# CindyLou_Main_Board_copy_2023-08-16.net
KiCad netlist of a schematic drawn in Altium Designer
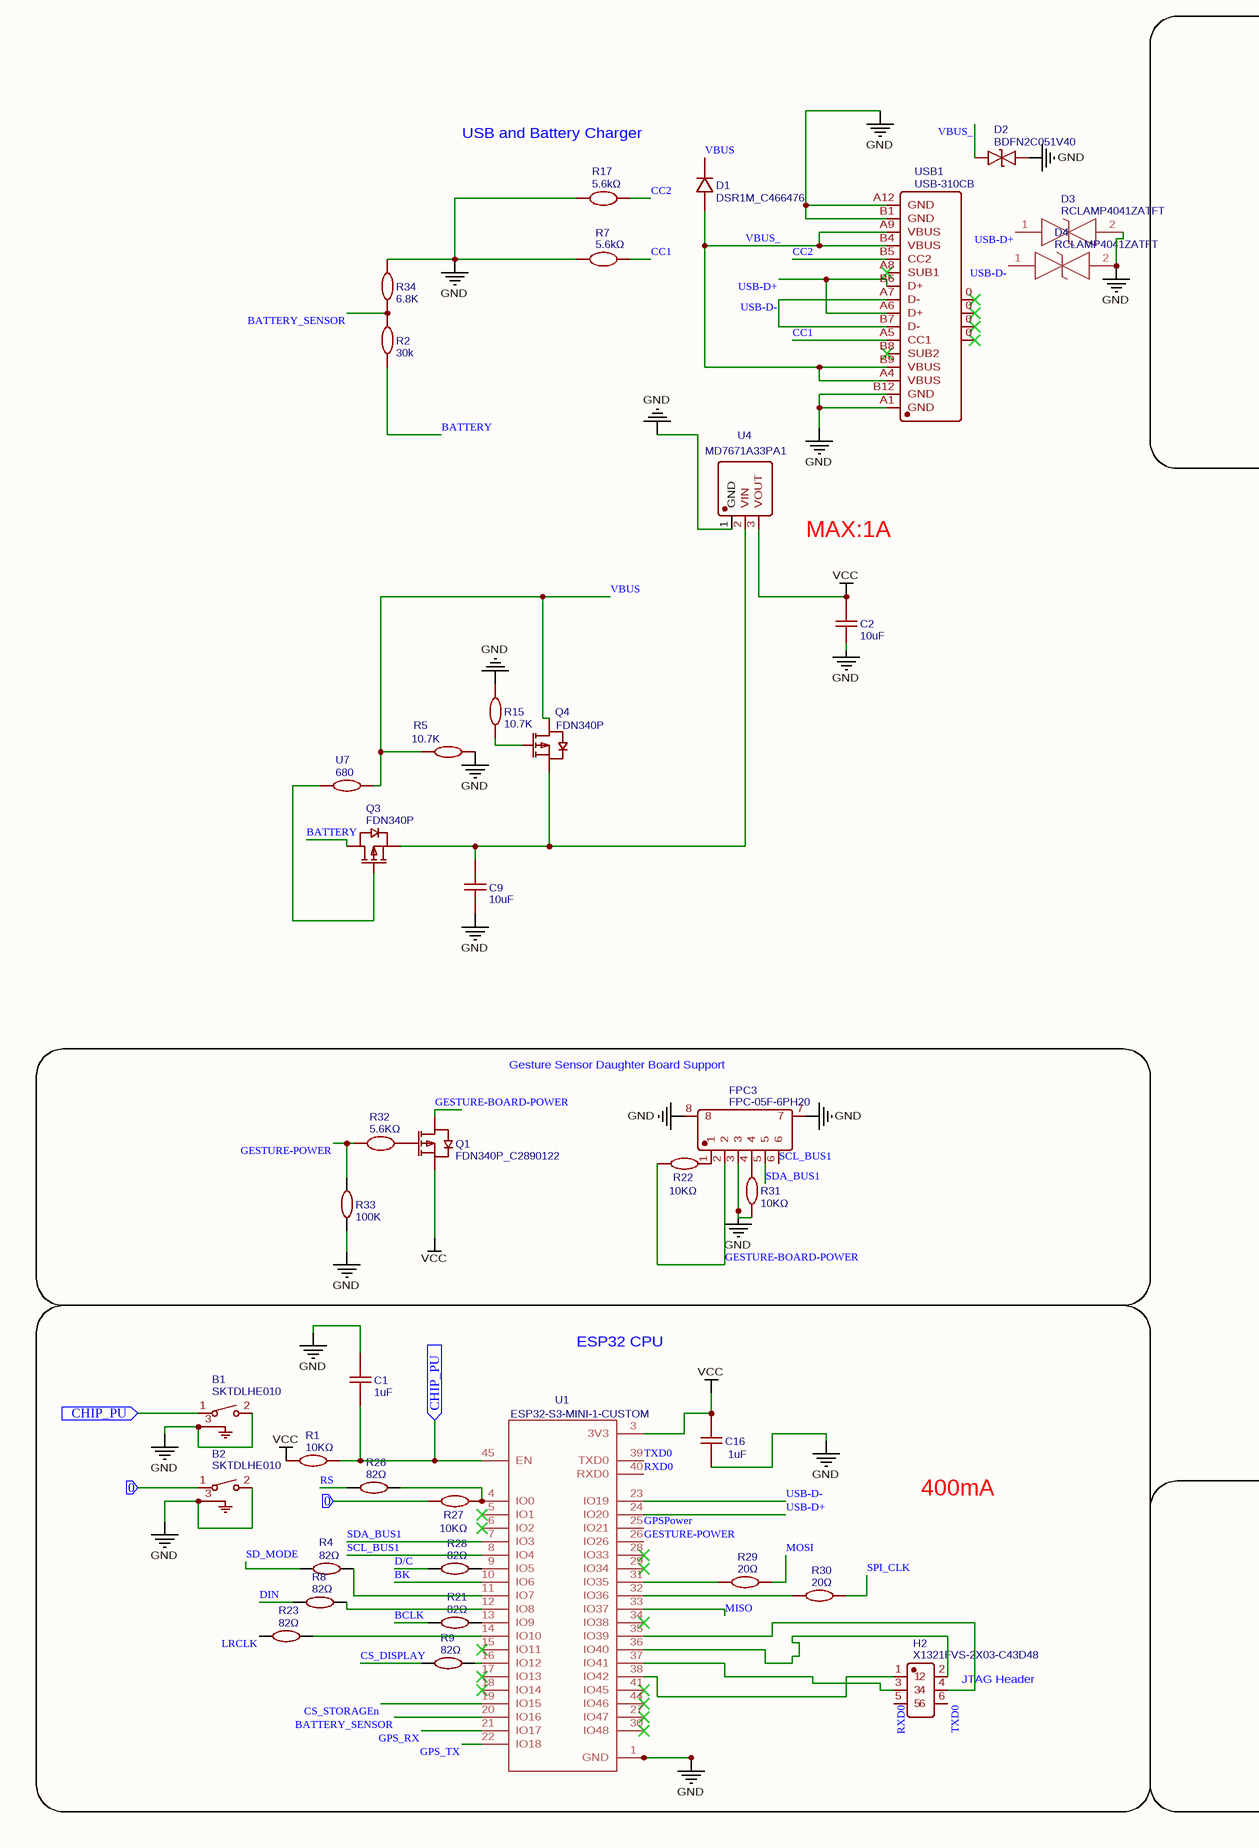
[diagram p0: CindyLou Main Board copy_2023-08-16.schdoc, left]
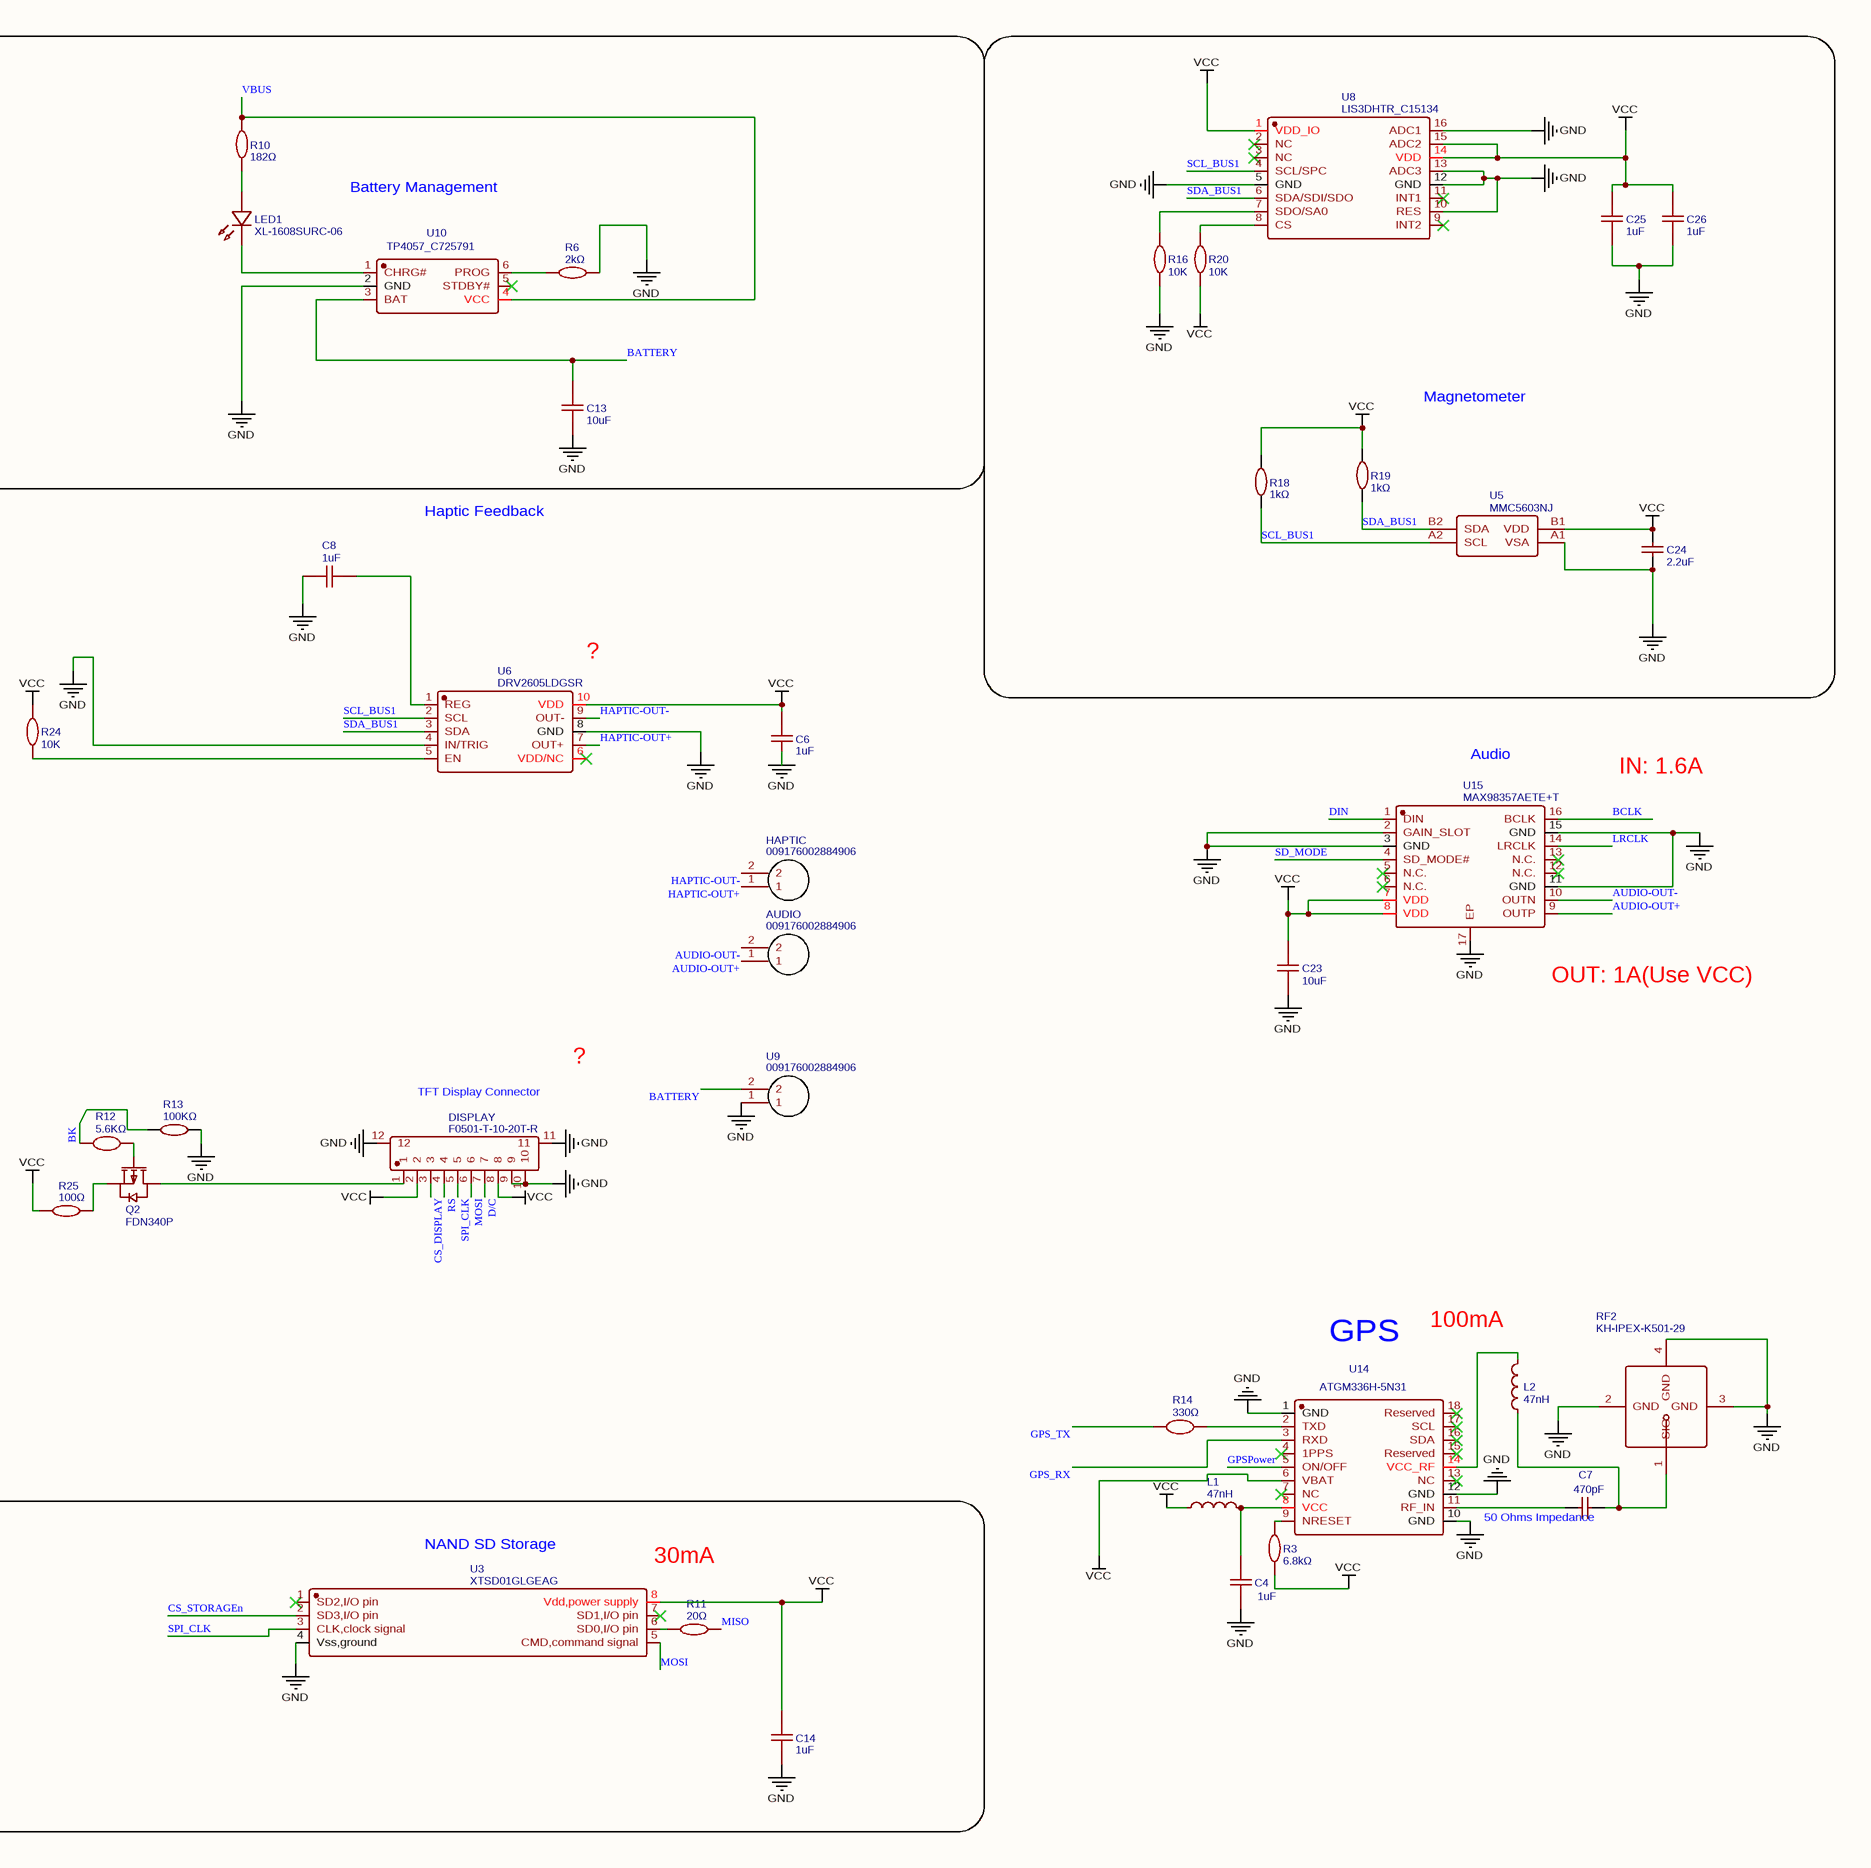
[diagram p1: CindyLou Main Board copy_2023-08-16.schdoc, right]

(export (version "E")
  (design (tool "Eeschema 10.0.6"))
  (components
    (comp (ref "AUDIO")
      (value "009176002884906")
      (footprint "009176002884906")
      (fields (field (name "CONTRIBUTOR") "Av448"))
      (libsource (lib "altium-import") (part "root_0_009176002884906_"))
    )
    (comp (ref "B1")
      (value "SKTDLHE010")
      (footprint "KEY-SMD_SKTDLHE010")
      (fields (field (name "MANUFACTURER") "ALPS Electric") (field (name "CONTRIBUTOR") "LCSC"))
      (libsource (lib "altium-import") (part "root_0_SKTDLHE010_"))
    )
    (comp (ref "B2")
      (value "SKTDLHE010")
      (footprint "KEY-SMD_SKTDLHE010")
      (fields (field (name "MANUFACTURER") "ALPS Electric") (field (name "CONTRIBUTOR") "LCSC"))
      (libsource (lib "altium-import") (part "root_0_SKTDLHE010_"))
    )
    (comp (ref "C1")
      (value "1uF")
      (footprint "C0402")
      (fields
        (field (name "MANUFACTURER") "muRata(村田)")
        (field (name "MANUFACTURER PART") "GRT155R70J105KE01D")
        (field (name "CONTRIBUTOR") "LCSC")
      )
      (libsource (lib "altium-import") (part "root_1_1uF_"))
    )
    (comp (ref "C2")
      (value "10uF")
      (footprint "C0402")
      (fields
        (field (name "MANUFACTURER") "SAMSUNG(三星)")
        (field (name "MANUFACTURER PART") "CL05A106MQ5NUNZ")
        (field (name "CONTRIBUTOR") "LCSC")
      )
      (libsource (lib "altium-import") (part "root_3_10uF_"))
    )
    (comp (ref "C4")
      (value "1uF")
      (footprint "C0402")
      (fields
        (field (name "MANUFACTURER") "muRata(村田)")
        (field (name "MANUFACTURER PART") "GRT155R70J105KE01D")
        (field (name "CONTRIBUTOR") "LCSC")
      )
      (libsource (lib "altium-import") (part "root_1_1uF_"))
    )
    (comp (ref "C6")
      (value "1uF")
      (footprint "C0402")
      (fields
        (field (name "MANUFACTURER") "muRata(村田)")
        (field (name "MANUFACTURER PART") "GRT155R70J105KE01D")
        (field (name "CONTRIBUTOR") "LCSC")
      )
      (libsource (lib "altium-import") (part "root_1_1uF_"))
    )
    (comp (ref "C7")
      (value "470pF")
      (footprint "C0201")
      (fields (field (name "MANUFACTURER PART") "0201B471K500NT") (field (name "MANUFACTURER") "FH"))
      (libsource (lib "altium-import") (part "root_0_470pF_"))
    )
    (comp (ref "C8")
      (value "1uF")
      (footprint "C0201")
      (fields
        (field (name "MANUFACTURER") "SANYEAR")
        (field (name "MANUFACTURER PART") "C0201X5R105M6R3NT")
        (field (name "CONTRIBUTOR") "LCSC")
      )
      (libsource (lib "altium-import") (part "root_0_1uF_"))
    )
    (comp (ref "C9")
      (value "10uF")
      (footprint "C0402")
      (fields
        (field (name "MANUFACTURER") "SAMSUNG(三星)")
        (field (name "MANUFACTURER PART") "CL05A106MQ5NUNZ")
        (field (name "CONTRIBUTOR") "LCSC")
      )
      (libsource (lib "altium-import") (part "root_1_10uF_"))
    )
    (comp (ref "C13")
      (value "10uF")
      (footprint "C0402")
      (fields
        (field (name "MANUFACTURER") "SAMSUNG(三星)")
        (field (name "MANUFACTURER PART") "CL05A106MQ5NUNZ")
        (field (name "CONTRIBUTOR") "LCSC")
      )
      (libsource (lib "altium-import") (part "root_1_10uF_"))
    )
    (comp (ref "C14")
      (value "1uF")
      (footprint "C0402")
      (fields
        (field (name "MANUFACTURER") "muRata(村田)")
        (field (name "MANUFACTURER PART") "GRT155R70J105KE01D")
        (field (name "CONTRIBUTOR") "LCSC")
      )
      (libsource (lib "altium-import") (part "root_1_1uF_"))
    )
    (comp (ref "C16")
      (value "1uF")
      (footprint "C0402")
      (fields
        (field (name "MANUFACTURER") "muRata(村田)")
        (field (name "MANUFACTURER PART") "GRT155R70J105KE01D")
        (field (name "CONTRIBUTOR") "LCSC")
      )
      (libsource (lib "altium-import") (part "root_1_1uF_"))
    )
    (comp (ref "C23")
      (value "10uF")
      (footprint "C0402")
      (fields
        (field (name "MANUFACTURER") "SAMSUNG(三星)")
        (field (name "MANUFACTURER PART") "CL05A106MQ5NUNZ")
        (field (name "CONTRIBUTOR") "LCSC")
      )
      (libsource (lib "altium-import") (part "root_1_10uF_"))
    )
    (comp (ref "C24")
      (value "2.2uF")
      (footprint "C0402")
      (fields (field (name "MANUFACTURER PART") "GRM155R61A225KE95D") (field (name "MANUFACTURER") "MuRata"))
      (libsource (lib "altium-import") (part "root_1_2.2uF_"))
    )
    (comp (ref "C25")
      (value "1uF")
      (footprint "C0402")
      (fields
        (field (name "MANUFACTURER") "muRata(村田)")
        (field (name "MANUFACTURER PART") "GRT155R70J105KE01D")
        (field (name "CONTRIBUTOR") "LCSC")
      )
      (libsource (lib "altium-import") (part "root_1_1uF_"))
    )
    (comp (ref "C26")
      (value "1uF")
      (footprint "C0402")
      (fields
        (field (name "MANUFACTURER") "muRata(村田)")
        (field (name "MANUFACTURER PART") "GRT155R70J105KE01D")
        (field (name "CONTRIBUTOR") "LCSC")
      )
      (libsource (lib "altium-import") (part "root_1_1uF_"))
    )
    (comp (ref "D1")
      (value "DSR1M_C466476")
      (footprint "SOD-123FL_L2.8-W1.8-LS3.7-RD")
      (fields
        (field (name "MANUFACTURER") "High Diode(海德)")
        (field (name "MANUFACTURER PART") "DSR1M")
        (field (name "CONTRIBUTOR") "LCSC")
      )
      (libsource (lib "altium-import") (part "root_3_DSR1M_C466476_"))
    )
    (comp (ref "D2")
      (value "BDFN2C051V40")
      (footprint "DFN-SMD_L1.0-W0.6-BI")
      (fields (field (name "MANUFACTURER") "BORN(伯恩半导体)") (field (name "CONTRIBUTOR") "LCSC"))
      (libsource (lib "altium-import") (part "root_0_BDFN2C051V40_"))
    )
    (comp (ref "D3")
      (value "RCLAMP4041ZATFT")
      (footprint "RCLAMP4021ZATFT")
      (fields (field (name "CONTRIBUTOR") "dparker"))
      (libsource (lib "altium-import") (part "root_0_RCLAMP4041ZATFT_"))
    )
    (comp (ref "D4")
      (value "RCLAMP4041ZATFT")
      (footprint "RCLAMP4021ZATFT")
      (fields (field (name "CONTRIBUTOR") "dparker"))
      (libsource (lib "altium-import") (part "root_0_RCLAMP4041ZATFT_"))
    )
    (comp (ref "DISPLAY")
      (value "F0501-T-10-20T-R")
      (footprint "FPC-SMD_F0501-T-10-20T-R")
      (fields (field (name "MANUFACTURER") "XFCN(兴飞)") (field (name "CONTRIBUTOR") "LCSC"))
      (libsource (lib "altium-import") (part "root_1_F0501-T-10-20T-R_"))
    )
    (comp (ref "FPC3")
      (value "FPC-05F-6PH20")
      (footprint "FPC-SMD_6P-P0.50_XUNPU_FPC-05F-6PH20")
      (fields (field (name "MANUFACTURER") "XUNPU(讯普)") (field (name "CONTRIBUTOR") "LCSC"))
      (libsource (lib "altium-import") (part "root_1_FPC-05F-6PH20_"))
    )
    (comp (ref "H2")
      (value "X1321FVS-2X03-C43D48")
      (footprint "HDR-SMD_6P-P1.27-V-F-R2-C3-LS4.8")
      (fields
        (field (name "MANUFACTURER") "XKB Connectivity(中国星坤)")
        (field (name "MANUFACTURER PART") "X1321FVS-2x03-C43D48")
        (field (name "CONTRIBUTOR") "LCSC")
      )
      (libsource (lib "altium-import") (part "root_0_X1321FVS-2X03-C43D48_"))
    )
    (comp (ref "HAPTIC")
      (value "009176002884906")
      (footprint "009176002884906")
      (fields (field (name "CONTRIBUTOR") "Av448"))
      (libsource (lib "altium-import") (part "root_0_009176002884906_"))
    )
    (comp (ref "L1")
      (value "47nH")
      (footprint "L0201")
      (fields
        (field (name "MANUFACTURER") "TDK")
        (field (name "MANUFACTURER PART") "MLG0603P47NHT000")
        (field (name "CONTRIBUTOR") "LCSC")
      )
      (libsource (lib "altium-import") (part "root_0_47nH_"))
    )
    (comp (ref "L2")
      (value "47nH")
      (footprint "L0201")
      (fields
        (field (name "MANUFACTURER") "TDK")
        (field (name "MANUFACTURER PART") "MLG0603P47NHT000")
        (field (name "CONTRIBUTOR") "LCSC")
      )
      (libsource (lib "altium-import") (part "root_1_47nH_"))
    )
    (comp (ref "LED1")
      (value "XL-1608SURC-06")
      (footprint "LED0603-RD_RED")
      (fields (field (name "MANUFACTURER") "XINGLIGHT(成兴光)") (field (name "CONTRIBUTOR") "LCSC"))
      (libsource (lib "altium-import") (part "root_1_XL-1608SURC-06_"))
    )
    (comp (ref "Q1")
      (value "FDN340P_C2890122")
      (footprint "SOT-23-3_L2.9-W1.3-P1.90-LS2.4-BR")
      (fields
        (field (name "MANUFACTURER") "TECH PUBLIC(台舟)")
        (field (name "MANUFACTURER PART") "FDN340P")
        (field (name "CONTRIBUTOR") "LCSC")
      )
      (libsource (lib "altium-import") (part "root_0_FDN340P_C2890122_"))
    )
    (comp (ref "Q2")
      (value "FDN340P")
      (footprint "SOT-23-3_L2.9-W1.3-P1.90-LS2.4-BR")
      (fields (field (name "MANUFACTURER") "TECH PUBLIC(台舟)") (field (name "CONTRIBUTOR") "LCSC"))
      (libsource (lib "altium-import") (part "root_3_FDN340P_"))
    )
    (comp (ref "Q3")
      (value "FDN340P")
      (footprint "SOT-23-3_L2.9-W1.3-P1.90-LS2.4-BR")
      (fields (field (name "MANUFACTURER") "TECH PUBLIC(台舟)") (field (name "CONTRIBUTOR") "LCSC"))
      (libsource (lib "altium-import") (part "root_1_FDN340P_"))
    )
    (comp (ref "Q4")
      (value "FDN340P")
      (footprint "SOT-23-3_L2.9-W1.3-P1.90-LS2.4-BR")
      (fields (field (name "MANUFACTURER") "TECH PUBLIC(台舟)") (field (name "CONTRIBUTOR") "LCSC"))
      (libsource (lib "altium-import") (part "root_0_FDN340P_"))
    )
    (comp (ref "R1")
      (value "10KΩ")
      (footprint "R0402")
      (fields
        (field (name "MANUFACTURER") "Stackpole Elec")
        (field (name "MANUFACTURER PART") "RNCF0402BTE10K0")
        (field (name "CONTRIBUTOR") "LCSC")
      )
      (libsource (lib "altium-import") (part "root_0_10KΩ_"))
    )
    (comp (ref "R2")
      (value "30k")
      (footprint "R0402")
      (fields
        (field (name "MANUFACTURER") "Susumu")
        (field (name "MANUFACTURER PART") "RR0510P-303-D")
        (field (name "CONTRIBUTOR") "LCSC")
      )
      (libsource (lib "altium-import") (part "root_1_30k_"))
    )
    (comp (ref "R3")
      (value "6.8kΩ")
      (footprint "R0402")
      (fields
        (field (name "MANUFACTURER") "ResistorToday")
        (field (name "MANUFACTURER PART") "AECR0402F6K80K9")
        (field (name "CONTRIBUTOR") "LCSC")
      )
      (libsource (lib "altium-import") (part "root_1_6.8kΩ_"))
    )
    (comp (ref "R4")
      (value "82Ω")
      (footprint "R0201")
      (fields (field (name "MANUFACTURER") "YAGEO") (field (name "MANUFACTURER PART") "AF0201JR-0782RL"))
      (libsource (lib "altium-import") (part "root_0_82Ω_"))
    )
    (comp (ref "R5")
      (value "10.7K")
      (footprint "R0402")
      (fields (field (name "MANUFACTURER PART") "SCR0402F10K7") (field (name "CONTRIBUTOR") "LCSC"))
      (libsource (lib "altium-import") (part "root_0_10.7K_"))
    )
    (comp (ref "R6")
      (value "2kΩ")
      (footprint "R0201")
      (fields
        (field (name "MANUFACTURER") "Uniroyal Elec")
        (field (name "MANUFACTURER PART") "0201WMF2001TEE")
        (field (name "CONTRIBUTOR") "LCSC")
      )
      (libsource (lib "altium-import") (part "root_0_2kΩ_"))
    )
    (comp (ref "R7")
      (value "5.6kΩ")
      (footprint "R0201")
      (fields
        (field (name "MANUFACTURER") "UNI-ROYAL(Uniroyal Elec)")
        (field (name "MANUFACTURER PART") "NQ01WMJ0562TEE")
        (field (name "CONTRIBUTOR") "LCSC")
      )
      (libsource (lib "altium-import") (part "root_0_5.6kΩ_"))
    )
    (comp (ref "R8")
      (value "82Ω")
      (footprint "R0201")
      (fields (field (name "MANUFACTURER") "YAGEO") (field (name "MANUFACTURER PART") "AF0201JR-0782RL"))
      (libsource (lib "altium-import") (part "root_0_82Ω_"))
    )
    (comp (ref "R9")
      (value "82Ω")
      (footprint "R0201")
      (fields (field (name "MANUFACTURER") "YAGEO") (field (name "MANUFACTURER PART") "AF0201JR-0782RL"))
      (libsource (lib "altium-import") (part "root_0_82Ω_"))
    )
    (comp (ref "R10")
      (value "182Ω")
      (footprint "R0402")
      (fields
        (field (name "MANUFACTURER") "Multicomp")
        (field (name "MANUFACTURER PART") "MCWR04X1820FTL")
        (field (name "CONTRIBUTOR") "LCSC")
      )
      (libsource (lib "altium-import") (part "root_1_182Ω_"))
    )
    (comp (ref "R11")
      (value "20Ω")
      (footprint "R0201")
      (fields (field (name "MANUFACTURER PART") "AC0201FR-0720RL") (field (name "CONTRIBUTOR") "LCSC"))
      (libsource (lib "altium-import") (part "root_0_20Ω_"))
    )
    (comp (ref "R12")
      (value "5.6KΩ")
      (footprint "R0402")
      (fields (field (name "MANUFACTURER PART") "RMC04025.6K5%N") (field (name "CONTRIBUTOR") "LCSC"))
      (libsource (lib "altium-import") (part "root_0_5.6KΩ_"))
    )
    (comp (ref "R13")
      (value "100KΩ")
      (footprint "R0402")
      (fields (field (name "MANUFACTURER") "YAGEO") (field (name "MANUFACTURER PART") "RC0402FR-07100KL"))
      (libsource (lib "altium-import") (part "root_2_100KΩ_"))
    )
    (comp (ref "R14")
      (value "330Ω")
      (footprint "R0201")
      (fields
        (field (name "MANUFACTURER") "UNI-ROYAL(Uniroyal Elec)")
        (field (name "MANUFACTURER PART") "0201WMJ0331TEE")
        (field (name "CONTRIBUTOR") "LCSC")
      )
      (libsource (lib "altium-import") (part "root_0_330Ω_"))
    )
    (comp (ref "R15")
      (value "10.7K")
      (footprint "R0402")
      (fields (field (name "MANUFACTURER PART") "SCR0402F10K7") (field (name "CONTRIBUTOR") "LCSC"))
      (libsource (lib "altium-import") (part "root_1_10.7K_"))
    )
    (comp (ref "R16")
      (value "10K")
      (footprint "R0402")
      (fields
        (field (name "MANUFACTURER") "ResistorToday")
        (field (name "MANUFACTURER PART") "AECR0402F10K0K9")
        (field (name "CONTRIBUTOR") "LCSC")
      )
      (libsource (lib "altium-import") (part "root_1_10K_"))
    )
    (comp (ref "R17")
      (value "5.6kΩ")
      (footprint "R0201")
      (fields
        (field (name "MANUFACTURER") "UNI-ROYAL(Uniroyal Elec)")
        (field (name "MANUFACTURER PART") "NQ01WMJ0562TEE")
        (field (name "CONTRIBUTOR") "LCSC")
      )
      (libsource (lib "altium-import") (part "root_2_5.6kΩ_"))
    )
    (comp (ref "R18")
      (value "1kΩ")
      (footprint "R0402")
      (fields
        (field (name "MANUFACTURER") "UNI-ROYAL(厚声)")
        (field (name "MANUFACTURER PART") "0402WGJ0102TCE")
      )
      (libsource (lib "altium-import") (part "root_1_1kΩ_"))
    )
    (comp (ref "R19")
      (value "1kΩ")
      (footprint "R0402")
      (fields
        (field (name "MANUFACTURER") "UNI-ROYAL(厚声)")
        (field (name "MANUFACTURER PART") "0402WGJ0102TCE")
      )
      (libsource (lib "altium-import") (part "root_1_1kΩ_"))
    )
    (comp (ref "R20")
      (value "10K")
      (footprint "R0402")
      (fields
        (field (name "MANUFACTURER") "ResistorToday")
        (field (name "MANUFACTURER PART") "AECR0402F10K0K9")
        (field (name "CONTRIBUTOR") "LCSC")
      )
      (libsource (lib "altium-import") (part "root_1_10K_"))
    )
    (comp (ref "R21")
      (value "82Ω")
      (footprint "R0201")
      (fields (field (name "MANUFACTURER") "YAGEO") (field (name "MANUFACTURER PART") "AF0201JR-0782RL"))
      (libsource (lib "altium-import") (part "root_0_82Ω_"))
    )
    (comp (ref "R22")
      (value "10KΩ")
      (footprint "R0402")
      (fields
        (field (name "MANUFACTURER") "Stackpole Elec")
        (field (name "MANUFACTURER PART") "RNCF0402BTE10K0")
        (field (name "CONTRIBUTOR") "LCSC")
      )
      (libsource (lib "altium-import") (part "root_0_10KΩ_"))
    )
    (comp (ref "R23")
      (value "82Ω")
      (footprint "R0201")
      (fields (field (name "MANUFACTURER") "YAGEO") (field (name "MANUFACTURER PART") "AF0201JR-0782RL"))
      (libsource (lib "altium-import") (part "root_0_82Ω_"))
    )
    (comp (ref "R24")
      (value "10K")
      (footprint "R0402")
      (fields
        (field (name "MANUFACTURER") "ResistorToday")
        (field (name "MANUFACTURER PART") "AECR0402F10K0K9")
        (field (name "CONTRIBUTOR") "LCSC")
      )
      (libsource (lib "altium-import") (part "root_1_10K_"))
    )
    (comp (ref "R25")
      (value "100Ω")
      (footprint "R0402")
      (fields
        (field (name "MANUFACTURER") "ResistorToday")
        (field (name "MANUFACTURER PART") "PTFR0402B100RN9")
        (field (name "CONTRIBUTOR") "LCSC")
      )
      (libsource (lib "altium-import") (part "root_0_100Ω_"))
    )
    (comp (ref "R26")
      (value "82Ω")
      (footprint "R0201")
      (fields (field (name "MANUFACTURER") "YAGEO") (field (name "MANUFACTURER PART") "AF0201JR-0782RL"))
      (libsource (lib "altium-import") (part "root_0_82Ω_"))
    )
    (comp (ref "R27")
      (value "10KΩ")
      (footprint "R0402")
      (fields
        (field (name "MANUFACTURER") "Stackpole Elec")
        (field (name "MANUFACTURER PART") "RNCF0402BTE10K0")
        (field (name "CONTRIBUTOR") "LCSC")
      )
      (libsource (lib "altium-import") (part "root_0_10KΩ_"))
    )
    (comp (ref "R28")
      (value "82Ω")
      (footprint "R0201")
      (fields (field (name "MANUFACTURER") "YAGEO") (field (name "MANUFACTURER PART") "AF0201JR-0782RL"))
      (libsource (lib "altium-import") (part "root_0_82Ω_"))
    )
    (comp (ref "R29")
      (value "20Ω")
      (footprint "R0201")
      (fields (field (name "CONTRIBUTOR") "LCSC"))
      (libsource (lib "altium-import") (part "root_0_20Ω_"))
    )
    (comp (ref "R30")
      (value "20Ω")
      (footprint "R0201")
      (fields (field (name "CONTRIBUTOR") "LCSC"))
      (libsource (lib "altium-import") (part "root_0_20Ω_"))
    )
    (comp (ref "R31")
      (value "10KΩ")
      (footprint "R0402")
      (fields
        (field (name "MANUFACTURER") "Stackpole Elec")
        (field (name "MANUFACTURER PART") "RNCF0402BTE10K0")
        (field (name "CONTRIBUTOR") "LCSC")
      )
      (libsource (lib "altium-import") (part "root_1_10KΩ_"))
    )
    (comp (ref "R32")
      (value "5.6KΩ")
      (footprint "R0402")
      (fields (field (name "MANUFACTURER PART") "RMC04025.6K5%N") (field (name "CONTRIBUTOR") "LCSC"))
      (libsource (lib "altium-import") (part "root_0_5.6KΩ_"))
    )
    (comp (ref "R33")
      (value "100K")
      (footprint "R0402")
      (fields (field (name "MANUFACTURER") "YAGEO") (field (name "MANUFACTURER PART") "RC0402FR-07100KL"))
      (libsource (lib "altium-import") (part "root_1_100K_"))
    )
    (comp (ref "R34")
      (value "6.8K")
      (footprint "R0402")
      (fields
        (field (name "MANUFACTURER") "ResistorToday")
        (field (name "MANUFACTURER PART") "HPCR0402F6K80K9")
        (field (name "CONTRIBUTOR") "LCSC")
      )
      (libsource (lib "altium-import") (part "root_1_6.8K_"))
    )
    (comp (ref "RF2")
      (value "KH-IPEX-K501-29")
      (footprint "ANT-SMD_KH-IPEX-K501-29")
      (fields (field (name "MANUFACTURER") "Shenzhen Kinghelm Elec") (field (name "CONTRIBUTOR") "LCSC"))
      (libsource (lib "altium-import") (part "root_0_KH-IPEX-K501-29_"))
    )
    (comp (ref "U1")
      (value "ESP32-S3-MINI-1-CUSTOM")
      (footprint "XCVR_ESP32-S3-MINI-1-N8-CUSTOM")
      (fields (field (name "CONTRIBUTOR") "Stefan Ravn van Overeem"))
      (libsource (lib "altium-import") (part "root_0_ESP32-S3-MINI-1-CUSTOM_"))
    )
    (comp (ref "U3")
      (value "XTSD01GLGEAG")
      (footprint "LGA-8_L6.0-W8.0-P1.27-BL")
      (fields (field (name "MANUFACTURER") "XTX") (field (name "CONTRIBUTOR") "LCSC"))
      (libsource (lib "altium-import") (part "root_0_XTSD01GLGEAG_"))
    )
    (comp (ref "U4")
      (value "MD7671A33PA1")
      (footprint "SOT-89-3_L4.5-W2.5-P1.50-LS4.2-BR")
      (fields (field (name "MANUFACTURER") "明达微") (field (name "CONTRIBUTOR") "LCSC"))
      (libsource (lib "altium-import") (part "root_1_MD7671A33PA1_"))
    )
    (comp (ref "U5")
      (value "MMC5603NJ")
      (footprint "FLIPCHIP-4_L0.8-W0.8-R2-C2-P0.40-TL")
      (fields (field (name "MANUFACTURER") "MEMSIC(美新)") (field (name "CONTRIBUTOR") "LCSC"))
      (libsource (lib "altium-import") (part "root_2_MMC5603NJ_"))
    )
    (comp (ref "U6")
      (value "DRV2605LDGSR")
      (footprint "VSSOP-10_L3.0-W3.0-P0.50-LS4.9-BL")
      (fields (field (name "MANUFACTURER") "Texas Instruments") (field (name "CONTRIBUTOR") "LCSC"))
      (libsource (lib "altium-import") (part "root_0_DRV2605LDGSR_"))
    )
    (comp (ref "U7")
      (value "680")
      (footprint "R0402")
      (fields
        (field (name "MANUFACTURER") "ResistorToday")
        (field (name "MANUFACTURER PART") "HPCR0402F680RK9")
        (field (name "CONTRIBUTOR") "LCSC")
      )
      (libsource (lib "altium-import") (part "root_2_680_"))
    )
    (comp (ref "U8")
      (value "LIS3DHTR_C15134")
      (footprint "LGA-16_L3.0-W3.0-P0.50-TL")
      (fields (field (name "MANUFACTURER PART") "LIS3DHTR") (field (name "MANUFACTURER") "ST(意法半导体)"))
      (libsource (lib "altium-import") (part "root_0_LIS3DHTR_C15134_"))
    )
    (comp (ref "U9")
      (value "009176002884906")
      (footprint "009176002884906")
      (fields (field (name "CONTRIBUTOR") "Av448"))
      (libsource (lib "altium-import") (part "root_0_009176002884906_"))
    )
    (comp (ref "U10")
      (value "TP4057_C725791")
      (footprint "SOT-23-6_L2.9-W1.6-P0.95-LS2.8-BR")
      (fields
        (field (name "MANUFACTURER") "UMW(Youtai Semiconductor Co., Ltd.)")
        (field (name "MANUFACTURER PART") "TP4057")
        (field (name "CONTRIBUTOR") "LCSC")
      )
      (libsource (lib "altium-import") (part "root_0_TP4057_C725791_"))
    )
    (comp (ref "U14")
      (value "ATGM336H-5N31")
      (footprint "GPSM-SMD_ATGM336H-TR")
      (fields (field (name "MANUFACTURER") "ZHONGKEWEI"))
      (libsource (lib "altium-import") (part "root_0_ATGM336H-5N31_"))
    )
    (comp (ref "U15")
      (value "MAX98357AETE+T")
      (footprint "TQFN-16_L3.0-W3.0-P0.50-BL-EP1.5")
      (fields (field (name "MANUFACTURER") "MAXIM(美信)") (field (name "CONTRIBUTOR") "LCSC"))
      (libsource (lib "altium-import") (part "root_0_MAX98357AETE+T_"))
    )
    (comp (ref "USB1")
      (value "USB-310CB")
      (footprint "USB-C-SMD_20P-P0.50-L6.5-W11.2")
      (fields (field (name "MANUFACTURER") "HOOYA") (field (name "CONTRIBUTOR") "LCSC"))
      (libsource (lib "altium-import") (part "root_2_USB-310CB_"))
    )
  )
  (nets
    (net (code "1") (name "/0") (class "Default")
      (node (ref "B2") (pin "1") (pinfunction "1_1") (pintype "passive"))
      (node (ref "R27") (pin "1") (pinfunction "1_1") (pintype "passive"))
    )
    (net (code "2") (name "/AUDIO-OUT+") (class "Default")
      (node (ref "AUDIO") (pin "1") (pinfunction "1_1") (pintype "passive"))
      (node (ref "U15") (pin "9") (pinfunction "OUTP_9") (pintype "passive"))
    )
    (net (code "3") (name "/AUDIO-OUT-") (class "Default")
      (node (ref "AUDIO") (pin "2") (pinfunction "2_2") (pintype "passive"))
      (node (ref "U15") (pin "10") (pinfunction "OUTN_10") (pintype "passive"))
    )
    (net (code "4") (name "/BATTERY") (class "Default")
      (node (ref "C13") (pin "2") (pinfunction "2_2") (pintype "passive"))
      (node (ref "Q3") (pin "3") (pinfunction "D_3") (pintype "passive"))
      (node (ref "R2") (pin "1") (pinfunction "1_1") (pintype "passive"))
      (node (ref "U10") (pin "3") (pinfunction "BAT_3") (pintype "passive"))
      (node (ref "U9") (pin "2") (pinfunction "2_2") (pintype "passive"))
    )
    (net (code "5") (name "/BATTERY_SENSOR") (class "Default")
      (node (ref "R2") (pin "2") (pinfunction "2_2") (pintype "passive"))
      (node (ref "R34") (pin "1") (pinfunction "1_1") (pintype "passive"))
      (node (ref "U1") (pin "20") (pinfunction "IO16_20") (pintype "passive"))
    )
    (net (code "6") (name "/BCLK") (class "Default")
      (node (ref "R21") (pin "1") (pinfunction "1_1") (pintype "passive"))
      (node (ref "U15") (pin "16") (pinfunction "BCLK_16") (pintype "passive"))
    )
    (net (code "7") (name "/BK") (class "Default")
      (node (ref "R12") (pin "1") (pinfunction "1_1") (pintype "passive"))
      (node (ref "R13") (pin "2") (pinfunction "2_2") (pintype "passive"))
      (node (ref "U1") (pin "10") (pinfunction "IO6_10") (pintype "passive"))
    )
    (net (code "8") (name "/CC1") (class "Default")
      (node (ref "R7") (pin "2") (pinfunction "2_2") (pintype "passive"))
      (node (ref "USB1") (pin "A5") (pinfunction "CC1_A5") (pintype "passive"))
    )
    (net (code "9") (name "/CC2") (class "Default")
      (node (ref "R17") (pin "1") (pinfunction "1_1") (pintype "passive"))
      (node (ref "USB1") (pin "B5") (pinfunction "CC2_B5") (pintype "passive"))
    )
    (net (code "10") (name "/CHIP_PU") (class "Default")
      (node (ref "B1") (pin "1") (pinfunction "1_1") (pintype "passive"))
      (node (ref "C1") (pin "1") (pinfunction "1_1") (pintype "passive"))
      (node (ref "R1") (pin "2") (pinfunction "2_2") (pintype "passive"))
      (node (ref "U1") (pin "45") (pinfunction "EN_45") (pintype "passive"))
    )
    (net (code "11") (name "/CS_DISPLAY") (class "Default")
      (node (ref "DISPLAY") (pin "3") (pinfunction "3_3") (pintype "passive"))
      (node (ref "R9") (pin "1") (pinfunction "1_1") (pintype "passive"))
    )
    (net (code "12") (name "/CS_STORAGEn") (class "Default")
      (node (ref "U1") (pin "19") (pinfunction "IO15_19") (pintype "passive"))
      (node (ref "U3") (pin "2") (pinfunction "SD3,I/O_pin_2") (pintype "passive"))
    )
    (net (code "13") (name "/DIN") (class "Default")
      (node (ref "R8") (pin "1") (pinfunction "1_1") (pintype "passive"))
      (node (ref "U15") (pin "1") (pinfunction "DIN_1") (pintype "passive"))
    )
    (net (code "14") (name "/D{slash}C") (class "Default")
      (node (ref "DISPLAY") (pin "7") (pinfunction "7_7") (pintype "passive"))
      (node (ref "R28") (pin "1") (pinfunction "1_1") (pintype "passive"))
    )
    (net (code "15") (name "/GESTURE-BOARD-POWER") (class "Default")
      (node (ref "FPC3") (pin "2") (pinfunction "2_2") (pintype "passive"))
      (node (ref "Q1") (pin "3") (pinfunction "D_3") (pintype "passive"))
      (node (ref "R22") (pin "1") (pinfunction "1_1") (pintype "passive"))
    )
    (net (code "16") (name "/GESTURE-POWER") (class "Default")
      (node (ref "R32") (pin "1") (pinfunction "1_1") (pintype "passive"))
      (node (ref "R33") (pin "2") (pinfunction "2_2") (pintype "passive"))
      (node (ref "U1") (pin "26") (pinfunction "IO26_26") (pintype "passive"))
    )
    (net (code "17") (name "/GPSPower") (class "Default")
      (node (ref "U1") (pin "25") (pinfunction "IO21_25") (pintype "passive"))
      (node (ref "U14") (pin "5") (pinfunction "ON/OFF_5") (pintype "passive"))
    )
    (net (code "18") (name "/GPS_RX") (class "Default")
      (node (ref "U1") (pin "21") (pinfunction "IO17_21") (pintype "passive"))
      (node (ref "U14") (pin "3") (pinfunction "RXD_3") (pintype "passive"))
    )
    (net (code "19") (name "/GPS_TX") (class "Default")
      (node (ref "R14") (pin "1") (pinfunction "1_1") (pintype "passive"))
      (node (ref "U1") (pin "22") (pinfunction "IO18_22") (pintype "passive"))
    )
    (net (code "20") (name "/HAPTIC-OUT+") (class "Default")
      (node (ref "HAPTIC") (pin "1") (pinfunction "1_1") (pintype "passive"))
      (node (ref "U6") (pin "7") (pinfunction "OUT+_7") (pintype "passive"))
    )
    (net (code "21") (name "/HAPTIC-OUT-") (class "Default")
      (node (ref "HAPTIC") (pin "2") (pinfunction "2_2") (pintype "passive"))
      (node (ref "U6") (pin "9") (pinfunction "OUT-_9") (pintype "passive"))
    )
    (net (code "22") (name "/LRCLK") (class "Default")
      (node (ref "R23") (pin "1") (pinfunction "1_1") (pintype "passive"))
      (node (ref "U15") (pin "14") (pinfunction "LRCLK_14") (pintype "passive"))
    )
    (net (code "23") (name "/MISO") (class "Default")
      (node (ref "R11") (pin "2") (pinfunction "2_2") (pintype "passive"))
      (node (ref "U1") (pin "33") (pinfunction "IO37_33") (pintype "passive"))
    )
    (net (code "24") (name "/MOSI") (class "Default")
      (node (ref "DISPLAY") (pin "6") (pinfunction "6_6") (pintype "passive"))
      (node (ref "R29") (pin "2") (pinfunction "2_2") (pintype "passive"))
      (node (ref "U3") (pin "5") (pinfunction "CMD,command_signal_5") (pintype "passive"))
    )
    (net (code "25") (name "/RS") (class "Default")
      (node (ref "DISPLAY") (pin "4") (pinfunction "4_4") (pintype "passive"))
      (node (ref "R26") (pin "1") (pinfunction "1_1") (pintype "passive"))
    )
    (net (code "26") (name "/RXD0") (class "Default")
      (node (ref "H2") (pin "5") (pinfunction "5_5") (pintype "passive"))
      (node (ref "U1") (pin "40") (pinfunction "RXD0_40") (pintype "passive"))
    )
    (net (code "27") (name "/SCL_BUS1") (class "Default")
      (node (ref "FPC3") (pin "6") (pinfunction "6_6") (pintype "passive"))
      (node (ref "R18") (pin "1") (pinfunction "1_1") (pintype "passive"))
      (node (ref "U1") (pin "8") (pinfunction "IO4_8") (pintype "passive"))
      (node (ref "U5") (pin "A2") (pinfunction "SCL_A2") (pintype "passive"))
      (node (ref "U6") (pin "2") (pinfunction "SCL_2") (pintype "passive"))
      (node (ref "U8") (pin "4") (pinfunction "SCL/SPC_4") (pintype "passive"))
    )
    (net (code "28") (name "/SDA_BUS1") (class "Default")
      (node (ref "FPC3") (pin "5") (pinfunction "5_5") (pintype "passive"))
      (node (ref "R19") (pin "1") (pinfunction "1_1") (pintype "passive"))
      (node (ref "U1") (pin "7") (pinfunction "IO3_7") (pintype "passive"))
      (node (ref "U5") (pin "B2") (pinfunction "SDA_B2") (pintype "passive"))
      (node (ref "U6") (pin "3") (pinfunction "SDA_3") (pintype "passive"))
      (node (ref "U8") (pin "6") (pinfunction "SDA/SDI/SDO_6") (pintype "passive"))
    )
    (net (code "29") (name "/SD_MODE") (class "Default")
      (node (ref "R4") (pin "1") (pinfunction "1_1") (pintype "passive"))
      (node (ref "U15") (pin "4") (pinfunction "SD_MODE#_4") (pintype "passive"))
    )
    (net (code "30") (name "/SPI_CLK") (class "Default")
      (node (ref "DISPLAY") (pin "5") (pinfunction "5_5") (pintype "passive"))
      (node (ref "R30") (pin "2") (pinfunction "2_2") (pintype "passive"))
      (node (ref "U3") (pin "3") (pinfunction "CLK,clock_signal_3") (pintype "passive"))
    )
    (net (code "31") (name "/TXD0") (class "Default")
      (node (ref "H2") (pin "6") (pinfunction "6_6") (pintype "passive"))
      (node (ref "U1") (pin "39") (pinfunction "TXD0_39") (pintype "passive"))
    )
    (net (code "32") (name "/USB-D+") (class "Default")
      (node (ref "D3") (pin "1") (pinfunction "1_1") (pintype "passive"))
      (node (ref "U1") (pin "24") (pinfunction "IO20_24") (pintype "passive"))
      (node (ref "USB1") (pin "A6") (pinfunction "D+_A6") (pintype "passive"))
      (node (ref "USB1") (pin "B6") (pinfunction "D+_B6") (pintype "passive"))
    )
    (net (code "33") (name "/USB-D-") (class "Default")
      (node (ref "D4") (pin "1") (pinfunction "1_1") (pintype "passive"))
      (node (ref "U1") (pin "23") (pinfunction "IO19_23") (pintype "passive"))
      (node (ref "USB1") (pin "A7") (pinfunction "D-_A7") (pintype "passive"))
      (node (ref "USB1") (pin "B7") (pinfunction "D-_B7") (pintype "passive"))
    )
    (net (code "34") (name "/VBUS") (class "Default")
      (node (ref "D1") (pin "1") (pinfunction "K_1") (pintype "passive"))
      (node (ref "Q4") (pin "3") (pinfunction "D_3") (pintype "passive"))
      (node (ref "R10") (pin "2") (pinfunction "2_2") (pintype "passive"))
      (node (ref "R5") (pin "1") (pinfunction "1_1") (pintype "passive"))
      (node (ref "U10") (pin "4") (pinfunction "VCC_4") (pintype "passive"))
      (node (ref "U7") (pin "1") (pinfunction "1_1") (pintype "passive"))
    )
    (net (code "35") (name "/VBUS_") (class "Default")
      (node (ref "D1") (pin "2") (pinfunction "A_2") (pintype "passive"))
      (node (ref "D2") (pin "1") (pinfunction "1_1") (pintype "passive"))
      (node (ref "USB1") (pin "A4") (pinfunction "VBUS_A4") (pintype "passive"))
      (node (ref "USB1") (pin "A9") (pinfunction "VBUS_A9") (pintype "passive"))
      (node (ref "USB1") (pin "B4") (pinfunction "VBUS_B4") (pintype "passive"))
      (node (ref "USB1") (pin "B9") (pinfunction "VBUS_B9") (pintype "passive"))
    )
    (net (code "36") (name "GND") (class "Default")
      (node (ref "B1") (pin "2") (pinfunction "2_2") (pintype "passive"))
      (node (ref "B1") (pin "3") (pinfunction "GND_3") (pintype "passive"))
      (node (ref "B2") (pin "2") (pinfunction "2_2") (pintype "passive"))
      (node (ref "B2") (pin "3") (pinfunction "GND_3") (pintype "passive"))
      (node (ref "C1") (pin "2") (pinfunction "2_2") (pintype "passive"))
      (node (ref "C13") (pin "1") (pinfunction "1_1") (pintype "passive"))
      (node (ref "C14") (pin "1") (pinfunction "1_1") (pintype "passive"))
      (node (ref "C16") (pin "1") (pinfunction "1_1") (pintype "passive"))
      (node (ref "C2") (pin "2") (pinfunction "2_2") (pintype "passive"))
      (node (ref "C23") (pin "1") (pinfunction "1_1") (pintype "passive"))
      (node (ref "C24") (pin "1") (pinfunction "1_1") (pintype "passive"))
      (node (ref "C25") (pin "1") (pinfunction "1_1") (pintype "passive"))
      (node (ref "C26") (pin "1") (pinfunction "1_1") (pintype "passive"))
      (node (ref "C4") (pin "1") (pinfunction "1_1") (pintype "passive"))
      (node (ref "C6") (pin "1") (pinfunction "1_1") (pintype "passive"))
      (node (ref "C8") (pin "1") (pinfunction "1_1") (pintype "passive"))
      (node (ref "C9") (pin "1") (pinfunction "1_1") (pintype "passive"))
      (node (ref "D2") (pin "2") (pinfunction "2_2") (pintype "passive"))
      (node (ref "D3") (pin "2") (pinfunction "2_2") (pintype "passive"))
      (node (ref "D4") (pin "2") (pinfunction "2_2") (pintype "passive"))
      (node (ref "DISPLAY") (pin "10") (pinfunction "10_10") (pintype "passive"))
      (node (ref "DISPLAY") (pin "11") (pinfunction "11_11") (pintype "passive"))
      (node (ref "DISPLAY") (pin "12") (pinfunction "12_12") (pintype "passive"))
      (node (ref "DISPLAY") (pin "9") (pinfunction "9_9") (pintype "passive"))
      (node (ref "FPC3") (pin "3") (pinfunction "3_3") (pintype "passive"))
      (node (ref "FPC3") (pin "7") (pinfunction "7_7") (pintype "passive"))
      (node (ref "FPC3") (pin "8") (pinfunction "8_8") (pintype "passive"))
      (node (ref "R13") (pin "1") (pinfunction "1_1") (pintype "passive"))
      (node (ref "R15") (pin "2") (pinfunction "2_2") (pintype "passive"))
      (node (ref "R16") (pin "1") (pinfunction "1_1") (pintype "passive"))
      (node (ref "R17") (pin "2") (pinfunction "2_2") (pintype "passive"))
      (node (ref "R31") (pin "1") (pinfunction "1_1") (pintype "passive"))
      (node (ref "R33") (pin "1") (pinfunction "1_1") (pintype "passive"))
      (node (ref "R34") (pin "2") (pinfunction "2_2") (pintype "passive"))
      (node (ref "R5") (pin "2") (pinfunction "2_2") (pintype "passive"))
      (node (ref "R6") (pin "2") (pinfunction "2_2") (pintype "passive"))
      (node (ref "R7") (pin "1") (pinfunction "1_1") (pintype "passive"))
      (node (ref "RF2") (pin "2") (pinfunction "GND_2") (pintype "passive"))
      (node (ref "RF2") (pin "3") (pinfunction "GND_3") (pintype "passive"))
      (node (ref "RF2") (pin "4") (pinfunction "GND_4") (pintype "passive"))
      (node (ref "U1") (pin "1") (pinfunction "GND_1") (pintype "passive"))
      (node (ref "U1") (pin "2") (pinfunction "GND_2") (pintype "passive"))
      (node (ref "U1") (pin "42") (pinfunction "GND_42") (pintype "passive"))
      (node (ref "U1") (pin "43") (pinfunction "GND_43") (pintype "passive"))
      (node (ref "U1") (pin "46") (pinfunction "GND_46") (pintype "passive"))
      (node (ref "U1") (pin "47") (pinfunction "GND_47") (pintype "passive"))
      (node (ref "U1") (pin "48") (pinfunction "GND_48") (pintype "passive"))
      (node (ref "U1") (pin "49") (pinfunction "GND_49") (pintype "passive"))
      (node (ref "U1") (pin "50") (pinfunction "GND_50") (pintype "passive"))
      (node (ref "U1") (pin "51") (pinfunction "GND_51") (pintype "passive"))
      (node (ref "U1") (pin "52") (pinfunction "GND_52") (pintype "passive"))
      (node (ref "U1") (pin "53") (pinfunction "GND_53") (pintype "passive"))
      (node (ref "U1") (pin "54") (pinfunction "GND_54") (pintype "passive"))
      (node (ref "U1") (pin "55") (pinfunction "GND_55") (pintype "passive"))
      (node (ref "U1") (pin "56") (pinfunction "GND_56") (pintype "passive"))
      (node (ref "U1") (pin "57") (pinfunction "GND_57") (pintype "passive"))
      (node (ref "U1") (pin "58") (pinfunction "GND_58") (pintype "passive"))
      (node (ref "U1") (pin "59") (pinfunction "GND_59") (pintype "passive"))
      (node (ref "U1") (pin "60") (pinfunction "GND_60") (pintype "passive"))
      (node (ref "U1") (pin "62") (pinfunction "GND_62") (pintype "passive"))
      (node (ref "U1") (pin "63") (pinfunction "GND_63") (pintype "passive"))
      (node (ref "U1") (pin "64") (pinfunction "GND_64") (pintype "passive"))
      (node (ref "U1") (pin "65") (pinfunction "GND_65") (pintype "passive"))
      (node (ref "U10") (pin "2") (pinfunction "GND_2") (pintype "passive"))
      (node (ref "U14") (pin "1") (pinfunction "GND_1") (pintype "passive"))
      (node (ref "U14") (pin "10") (pinfunction "GND_10") (pintype "passive"))
      (node (ref "U14") (pin "12") (pinfunction "GND_12") (pintype "passive"))
      (node (ref "U15") (pin "11") (pinfunction "GND_11") (pintype "passive"))
      (node (ref "U15") (pin "15") (pinfunction "GND_15") (pintype "passive"))
      (node (ref "U15") (pin "17") (pinfunction "EP_17") (pintype "passive"))
      (node (ref "U15") (pin "2") (pinfunction "GAIN_SLOT_2") (pintype "passive"))
      (node (ref "U15") (pin "3") (pinfunction "GND_3") (pintype "passive"))
      (node (ref "U3") (pin "4") (pinfunction "Vss,ground_4") (pintype "passive"))
      (node (ref "U4") (pin "1") (pinfunction "GND_1") (pintype "passive"))
      (node (ref "U5") (pin "A1") (pinfunction "VSA_A1") (pintype "passive"))
      (node (ref "U6") (pin "4") (pinfunction "IN/TRIG_4") (pintype "passive"))
      (node (ref "U6") (pin "8") (pinfunction "GND_8") (pintype "passive"))
      (node (ref "U8") (pin "10") (pinfunction "RES_10") (pintype "passive"))
      (node (ref "U8") (pin "12") (pinfunction "GND_12") (pintype "passive"))
      (node (ref "U8") (pin "13") (pinfunction "ADC3_13") (pintype "passive"))
      (node (ref "U8") (pin "16") (pinfunction "ADC1_16") (pintype "passive"))
      (node (ref "U8") (pin "5") (pinfunction "GND_5") (pintype "passive"))
      (node (ref "U9") (pin "1") (pinfunction "1_1") (pintype "passive"))
      (node (ref "USB1") (pin "A1") (pinfunction "GND_A1") (pintype "passive"))
      (node (ref "USB1") (pin "A12") (pinfunction "GND_A12") (pintype "passive"))
      (node (ref "USB1") (pin "B1") (pinfunction "GND_B1") (pintype "passive"))
      (node (ref "USB1") (pin "B12") (pinfunction "GND_B12") (pintype "passive"))
    )
    (net (code "37") (name "Net-(FPC3-Pad1)") (class "Default")
      (node (ref "FPC3") (pin "1") (pinfunction "1_1") (pintype "passive"))
      (node (ref "R22") (pin "2") (pinfunction "2_2") (pintype "passive"))
    )
    (net (code "38") (name "Net-(FPC3-Pad4)") (class "Default")
      (node (ref "FPC3") (pin "4") (pinfunction "4_4") (pintype "passive"))
      (node (ref "R31") (pin "2") (pinfunction "2_2") (pintype "passive"))
    )
    (net (code "39") (name "Net-(LED1-A)") (class "Default")
      (node (ref "LED1") (pin "2") (pinfunction "A_2") (pintype "passive"))
      (node (ref "R10") (pin "1") (pinfunction "1_1") (pintype "passive"))
    )
    (net (code "40") (name "Net-(LED1-K)") (class "Default")
      (node (ref "LED1") (pin "1") (pinfunction "K_1") (pintype "passive"))
      (node (ref "U10") (pin "1") (pinfunction "CHRG#_1") (pintype "passive"))
    )
    (net (code "41") (name "Net-(Q1-G)") (class "Default")
      (node (ref "Q1") (pin "1") (pinfunction "G_1") (pintype "passive"))
      (node (ref "R32") (pin "2") (pinfunction "2_2") (pintype "passive"))
    )
    (net (code "42") (name "Net-(Q2-D)") (class "Default")
      (node (ref "DISPLAY") (pin "1") (pinfunction "1_1") (pintype "passive"))
      (node (ref "Q2") (pin "3") (pinfunction "D_3") (pintype "passive"))
    )
    (net (code "43") (name "Net-(Q2-G)") (class "Default")
      (node (ref "Q2") (pin "1") (pinfunction "G_1") (pintype "passive"))
      (node (ref "R12") (pin "2") (pinfunction "2_2") (pintype "passive"))
    )
    (net (code "44") (name "Net-(Q2-S)") (class "Default")
      (node (ref "Q2") (pin "2") (pinfunction "S_2") (pintype "passive"))
      (node (ref "R25") (pin "2") (pinfunction "2_2") (pintype "passive"))
    )
    (net (code "45") (name "Net-(Q3-G)") (class "Default")
      (node (ref "Q3") (pin "1") (pinfunction "G_1") (pintype "passive"))
      (node (ref "U7") (pin "2") (pinfunction "2_2") (pintype "passive"))
    )
    (net (code "46") (name "Net-(Q3-S)") (class "Default")
      (node (ref "C9") (pin "2") (pinfunction "2_2") (pintype "passive"))
      (node (ref "Q3") (pin "2") (pinfunction "S_2") (pintype "passive"))
      (node (ref "Q4") (pin "2") (pinfunction "S_2") (pintype "passive"))
      (node (ref "U4") (pin "2") (pinfunction "VIN_2") (pintype "passive"))
    )
    (net (code "47") (name "Net-(Q4-G)") (class "Default")
      (node (ref "Q4") (pin "1") (pinfunction "G_1") (pintype "passive"))
      (node (ref "R15") (pin "1") (pinfunction "1_1") (pintype "passive"))
    )
    (net (code "48") (name "Net-(RF2-SIG)") (class "Default")
      (node (ref "C7") (pin "2") (pinfunction "2_2") (pintype "passive"))
      (node (ref "L2") (pin "1") (pinfunction "1_1") (pintype "passive"))
      (node (ref "RF2") (pin "1") (pinfunction "SIG_1") (pintype "passive"))
    )
    (net (code "49") (name "Net-(U1-IO0)") (class "Default")
      (node (ref "R26") (pin "2") (pinfunction "2_2") (pintype "passive"))
      (node (ref "R27") (pin "2") (pinfunction "2_2") (pintype "passive"))
      (node (ref "U1") (pin "4") (pinfunction "IO0_4") (pintype "passive"))
    )
    (net (code "50") (name "Net-(U1-IO5)") (class "Default")
      (node (ref "R28") (pin "2") (pinfunction "2_2") (pintype "passive"))
      (node (ref "U1") (pin "9") (pinfunction "IO5_9") (pintype "passive"))
    )
    (net (code "51") (name "Net-(U1-IO7)") (class "Default")
      (node (ref "R4") (pin "2") (pinfunction "2_2") (pintype "passive"))
      (node (ref "U1") (pin "11") (pinfunction "IO7_11") (pintype "passive"))
    )
    (net (code "52") (name "Net-(U1-IO8)") (class "Default")
      (node (ref "R8") (pin "2") (pinfunction "2_2") (pintype "passive"))
      (node (ref "U1") (pin "12") (pinfunction "IO8_12") (pintype "passive"))
    )
    (net (code "53") (name "Net-(U1-IO9)") (class "Default")
      (node (ref "R21") (pin "2") (pinfunction "2_2") (pintype "passive"))
      (node (ref "U1") (pin "13") (pinfunction "IO9_13") (pintype "passive"))
    )
    (net (code "54") (name "Net-(U1-IO10)") (class "Default")
      (node (ref "R23") (pin "2") (pinfunction "2_2") (pintype "passive"))
      (node (ref "U1") (pin "14") (pinfunction "IO10_14") (pintype "passive"))
    )
    (net (code "55") (name "Net-(U1-IO12)") (class "Default")
      (node (ref "R9") (pin "2") (pinfunction "2_2") (pintype "passive"))
      (node (ref "U1") (pin "16") (pinfunction "IO12_16") (pintype "passive"))
    )
    (net (code "56") (name "Net-(U1-IO35)") (class "Default")
      (node (ref "R29") (pin "1") (pinfunction "1_1") (pintype "passive"))
      (node (ref "U1") (pin "31") (pinfunction "IO35_31") (pintype "passive"))
    )
    (net (code "57") (name "Net-(U1-IO36)") (class "Default")
      (node (ref "R30") (pin "1") (pinfunction "1_1") (pintype "passive"))
      (node (ref "U1") (pin "32") (pinfunction "IO36_32") (pintype "passive"))
    )
    (net (code "58") (name "Net-(U1-IO39)") (class "Default")
      (node (ref "H2") (pin "4") (pinfunction "4_4") (pintype "passive"))
      (node (ref "U1") (pin "35") (pinfunction "IO39_35") (pintype "passive"))
    )
    (net (code "59") (name "Net-(U1-IO40)") (class "Default")
      (node (ref "H2") (pin "2") (pinfunction "2_2") (pintype "passive"))
      (node (ref "U1") (pin "36") (pinfunction "IO40_36") (pintype "passive"))
    )
    (net (code "60") (name "Net-(U1-IO41)") (class "Default")
      (node (ref "H2") (pin "3") (pinfunction "3_3") (pintype "passive"))
      (node (ref "U1") (pin "37") (pinfunction "IO41_37") (pintype "passive"))
    )
    (net (code "61") (name "Net-(U1-IO42)") (class "Default")
      (node (ref "H2") (pin "1") (pinfunction "1_1") (pintype "passive"))
      (node (ref "U1") (pin "38") (pinfunction "IO42_38") (pintype "passive"))
    )
    (net (code "62") (name "Net-(U3-SD0,I{slash}O_pin)") (class "Default")
      (node (ref "R11") (pin "1") (pinfunction "1_1") (pintype "passive"))
      (node (ref "U3") (pin "6") (pinfunction "SD0,I/O_pin_6") (pintype "passive"))
    )
    (net (code "63") (name "Net-(U6-EN)") (class "Default")
      (node (ref "R24") (pin "1") (pinfunction "1_1") (pintype "passive"))
      (node (ref "U6") (pin "5") (pinfunction "EN_5") (pintype "passive"))
    )
    (net (code "64") (name "Net-(U6-REG)") (class "Default")
      (node (ref "C8") (pin "2") (pinfunction "2_2") (pintype "passive"))
      (node (ref "U6") (pin "1") (pinfunction "REG_1") (pintype "passive"))
    )
    (net (code "65") (name "Net-(U8-CS)") (class "Default")
      (node (ref "R20") (pin "2") (pinfunction "2_2") (pintype "passive"))
      (node (ref "U8") (pin "8") (pinfunction "CS_8") (pintype "passive"))
    )
    (net (code "66") (name "Net-(U8-SDO{slash}SA0)") (class "Default")
      (node (ref "R16") (pin "2") (pinfunction "2_2") (pintype "passive"))
      (node (ref "U8") (pin "7") (pinfunction "SDO/SA0_7") (pintype "passive"))
    )
    (net (code "67") (name "Net-(U10-PROG)") (class "Default")
      (node (ref "R6") (pin "1") (pinfunction "1_1") (pintype "passive"))
      (node (ref "U10") (pin "6") (pinfunction "PROG_6") (pintype "passive"))
    )
    (net (code "68") (name "Net-(U14-NRESET)") (class "Default")
      (node (ref "R3") (pin "2") (pinfunction "2_2") (pintype "passive"))
      (node (ref "U14") (pin "9") (pinfunction "NRESET_9") (pintype "passive"))
    )
    (net (code "69") (name "Net-(U14-RF_IN)") (class "Default")
      (node (ref "C7") (pin "1") (pinfunction "1_1") (pintype "passive"))
      (node (ref "U14") (pin "11") (pinfunction "RF_IN_11") (pintype "passive"))
    )
    (net (code "70") (name "Net-(U14-TXD)") (class "Default")
      (node (ref "R14") (pin "2") (pinfunction "2_2") (pintype "passive"))
      (node (ref "U14") (pin "2") (pinfunction "TXD_2") (pintype "passive"))
    )
    (net (code "71") (name "Net-(U14-VCC)") (class "Default")
      (node (ref "C4") (pin "2") (pinfunction "2_2") (pintype "passive"))
      (node (ref "L1") (pin "2") (pinfunction "2_2") (pintype "passive"))
      (node (ref "U14") (pin "8") (pinfunction "VCC_8") (pintype "passive"))
    )
    (net (code "72") (name "Net-(U14-VCC_RF)") (class "Default")
      (node (ref "L2") (pin "2") (pinfunction "2_2") (pintype "passive"))
      (node (ref "U14") (pin "14") (pinfunction "VCC_RF_14") (pintype "passive"))
    )
    (net (code "73") (name "VCC") (class "Default")
      (node (ref "C14") (pin "2") (pinfunction "2_2") (pintype "passive"))
      (node (ref "C16") (pin "2") (pinfunction "2_2") (pintype "passive"))
      (node (ref "C2") (pin "1") (pinfunction "1_1") (pintype "passive"))
      (node (ref "C23") (pin "2") (pinfunction "2_2") (pintype "passive"))
      (node (ref "C24") (pin "2") (pinfunction "2_2") (pintype "passive"))
      (node (ref "C25") (pin "2") (pinfunction "2_2") (pintype "passive"))
      (node (ref "C26") (pin "2") (pinfunction "2_2") (pintype "passive"))
      (node (ref "C6") (pin "2") (pinfunction "2_2") (pintype "passive"))
      (node (ref "DISPLAY") (pin "2") (pinfunction "2_2") (pintype "passive"))
      (node (ref "DISPLAY") (pin "8") (pinfunction "8_8") (pintype "passive"))
      (node (ref "L1") (pin "1") (pinfunction "1_1") (pintype "passive"))
      (node (ref "Q1") (pin "2") (pinfunction "S_2") (pintype "passive"))
      (node (ref "R1") (pin "1") (pinfunction "1_1") (pintype "passive"))
      (node (ref "R18") (pin "2") (pinfunction "2_2") (pintype "passive"))
      (node (ref "R19") (pin "2") (pinfunction "2_2") (pintype "passive"))
      (node (ref "R20") (pin "1") (pinfunction "1_1") (pintype "passive"))
      (node (ref "R24") (pin "2") (pinfunction "2_2") (pintype "passive"))
      (node (ref "R25") (pin "1") (pinfunction "1_1") (pintype "passive"))
      (node (ref "R3") (pin "1") (pinfunction "1_1") (pintype "passive"))
      (node (ref "U1") (pin "3") (pinfunction "3V3_3") (pintype "passive"))
      (node (ref "U14") (pin "6") (pinfunction "VBAT_6") (pintype "passive"))
      (node (ref "U15") (pin "7") (pinfunction "VDD_7") (pintype "passive"))
      (node (ref "U15") (pin "8") (pinfunction "VDD_8") (pintype "passive"))
      (node (ref "U3") (pin "8") (pinfunction "Vdd,power_supply_8") (pintype "passive"))
      (node (ref "U4") (pin "3") (pinfunction "VOUT_3") (pintype "passive"))
      (node (ref "U5") (pin "B1") (pinfunction "VDD_B1") (pintype "passive"))
      (node (ref "U6") (pin "10") (pinfunction "VDD_10") (pintype "passive"))
      (node (ref "U8") (pin "1") (pinfunction "VDD_IO_1") (pintype "passive"))
      (node (ref "U8") (pin "14") (pinfunction "VDD_14") (pintype "passive"))
      (node (ref "U8") (pin "15") (pinfunction "ADC2_15") (pintype "passive"))
    )
    (net (code "74") (name "unconnected-(U1-IO1-Pad5)") (class "Default")
      (node (ref "U1") (pin "5") (pinfunction "IO1_5") (pintype "passive+no_connect"))
    )
    (net (code "75") (name "unconnected-(U1-IO2-Pad6)") (class "Default")
      (node (ref "U1") (pin "6") (pinfunction "IO2_6") (pintype "passive+no_connect"))
    )
    (net (code "76") (name "unconnected-(U1-IO11-Pad15)") (class "Default")
      (node (ref "U1") (pin "15") (pinfunction "IO11_15") (pintype "passive+no_connect"))
    )
    (net (code "77") (name "unconnected-(U1-IO13-Pad17)") (class "Default")
      (node (ref "U1") (pin "17") (pinfunction "IO13_17") (pintype "passive+no_connect"))
    )
    (net (code "78") (name "unconnected-(U1-IO14-Pad18)") (class "Default")
      (node (ref "U1") (pin "18") (pinfunction "IO14_18") (pintype "passive+no_connect"))
    )
    (net (code "79") (name "unconnected-(U1-IO33-Pad28)") (class "Default")
      (node (ref "U1") (pin "28") (pinfunction "IO33_28") (pintype "passive+no_connect"))
    )
    (net (code "80") (name "unconnected-(U1-IO34-Pad29)") (class "Default")
      (node (ref "U1") (pin "29") (pinfunction "IO34_29") (pintype "passive+no_connect"))
    )
    (net (code "81") (name "unconnected-(U1-IO38-Pad34)") (class "Default")
      (node (ref "U1") (pin "34") (pinfunction "IO38_34") (pintype "passive+no_connect"))
    )
    (net (code "82") (name "unconnected-(U1-IO45-Pad41)") (class "Default")
      (node (ref "U1") (pin "41") (pinfunction "IO45_41") (pintype "passive+no_connect"))
    )
    (net (code "83") (name "unconnected-(U1-IO46-Pad44)") (class "Default")
      (node (ref "U1") (pin "44") (pinfunction "IO46_44") (pintype "passive+no_connect"))
    )
    (net (code "84") (name "unconnected-(U1-IO47-Pad27)") (class "Default")
      (node (ref "U1") (pin "27") (pinfunction "IO47_27") (pintype "passive+no_connect"))
    )
    (net (code "85") (name "unconnected-(U1-IO48-Pad30)") (class "Default")
      (node (ref "U1") (pin "30") (pinfunction "IO48_30") (pintype "passive+no_connect"))
    )
    (net (code "86") (name "unconnected-(U3-SD1,I{slash}O_pin-Pad7)") (class "Default")
      (node (ref "U3") (pin "7") (pinfunction "SD1,I/O_pin_7") (pintype "passive+no_connect"))
    )
    (net (code "87") (name "unconnected-(U3-SD2,I{slash}O_pin-Pad1)") (class "Default")
      (node (ref "U3") (pin "1") (pinfunction "SD2,I/O_pin_1") (pintype "passive+no_connect"))
    )
    (net (code "88") (name "unconnected-(U6-VDD{slash}NC-Pad6)") (class "Default")
      (node (ref "U6") (pin "6") (pinfunction "VDD/NC_6") (pintype "passive+no_connect"))
    )
    (net (code "89") (name "unconnected-(U8-INT1-Pad11)") (class "Default")
      (node (ref "U8") (pin "11") (pinfunction "INT1_11") (pintype "passive+no_connect"))
    )
    (net (code "90") (name "unconnected-(U8-INT2-Pad9)") (class "Default")
      (node (ref "U8") (pin "9") (pinfunction "INT2_9") (pintype "passive+no_connect"))
    )
    (net (code "91") (name "unconnected-(U8-NC-Pad2)") (class "Default")
      (node (ref "U8") (pin "2") (pinfunction "NC_2") (pintype "passive+no_connect"))
    )
    (net (code "92") (name "unconnected-(U8-NC-Pad3)") (class "Default")
      (node (ref "U8") (pin "3") (pinfunction "NC_3") (pintype "passive+no_connect"))
    )
    (net (code "93") (name "unconnected-(U10-STDBY#-Pad5)") (class "Default")
      (node (ref "U10") (pin "5") (pinfunction "STDBY#_5") (pintype "passive+no_connect"))
    )
    (net (code "94") (name "unconnected-(U14-1PPS-Pad4)") (class "Default")
      (node (ref "U14") (pin "4") (pinfunction "1PPS_4") (pintype "passive+no_connect"))
    )
    (net (code "95") (name "unconnected-(U14-NC-Pad7)") (class "Default")
      (node (ref "U14") (pin "7") (pinfunction "NC_7") (pintype "passive+no_connect"))
    )
    (net (code "96") (name "unconnected-(U14-NC-Pad13)") (class "Default")
      (node (ref "U14") (pin "13") (pinfunction "NC_13") (pintype "passive+no_connect"))
    )
    (net (code "97") (name "unconnected-(U14-Reserved-Pad15)") (class "Default")
      (node (ref "U14") (pin "15") (pinfunction "Reserved_15") (pintype "passive+no_connect"))
    )
    (net (code "98") (name "unconnected-(U14-Reserved-Pad18)") (class "Default")
      (node (ref "U14") (pin "18") (pinfunction "Reserved_18") (pintype "passive+no_connect"))
    )
    (net (code "99") (name "unconnected-(U14-SCL-Pad17)") (class "Default")
      (node (ref "U14") (pin "17") (pinfunction "SCL_17") (pintype "passive+no_connect"))
    )
    (net (code "100") (name "unconnected-(U14-SDA-Pad16)") (class "Default")
      (node (ref "U14") (pin "16") (pinfunction "SDA_16") (pintype "passive+no_connect"))
    )
    (net (code "101") (name "unconnected-(U15-N.C.-Pad5)") (class "Default")
      (node (ref "U15") (pin "5") (pinfunction "N.C._5") (pintype "passive+no_connect"))
    )
    (net (code "102") (name "unconnected-(U15-N.C.-Pad6)") (class "Default")
      (node (ref "U15") (pin "6") (pinfunction "N.C._6") (pintype "passive+no_connect"))
    )
    (net (code "103") (name "unconnected-(U15-N.C.-Pad12)") (class "Default")
      (node (ref "U15") (pin "12") (pinfunction "N.C._12") (pintype "passive+no_connect"))
    )
    (net (code "104") (name "unconnected-(U15-N.C.-Pad13)") (class "Default")
      (node (ref "U15") (pin "13") (pinfunction "N.C._13") (pintype "passive+no_connect"))
    )
    (net (code "105") (name "unconnected-(USB1-Pad0)") (class "Default")
      (node (ref "USB1") (pin "0") (pinfunction "0_0") (pintype "passive+no_connect"))
    )
    (net (code "106") (name "unconnected-(USB1-Pad0)_1") (class "Default")
      (node (ref "USB1") (pin "0") (pinfunction "0_0") (pintype "passive+no_connect"))
    )
    (net (code "107") (name "unconnected-(USB1-Pad0)_2") (class "Default")
      (node (ref "USB1") (pin "0") (pinfunction "0_0") (pintype "passive+no_connect"))
    )
    (net (code "108") (name "unconnected-(USB1-Pad0)_3") (class "Default")
      (node (ref "USB1") (pin "0") (pinfunction "0_0") (pintype "passive+no_connect"))
    )
    (net (code "109") (name "unconnected-(USB1-SUB1-PadA8)") (class "Default")
      (node (ref "USB1") (pin "A8") (pinfunction "SUB1_A8") (pintype "passive+no_connect"))
    )
    (net (code "110") (name "unconnected-(USB1-SUB2-PadB8)") (class "Default")
      (node (ref "USB1") (pin "B8") (pinfunction "SUB2_B8") (pintype "passive+no_connect"))
    )
  )
)
